# PMIC_RK809_RK3566_DDR4.net
KiCad netlist of a schematic drawn in Altium Designer
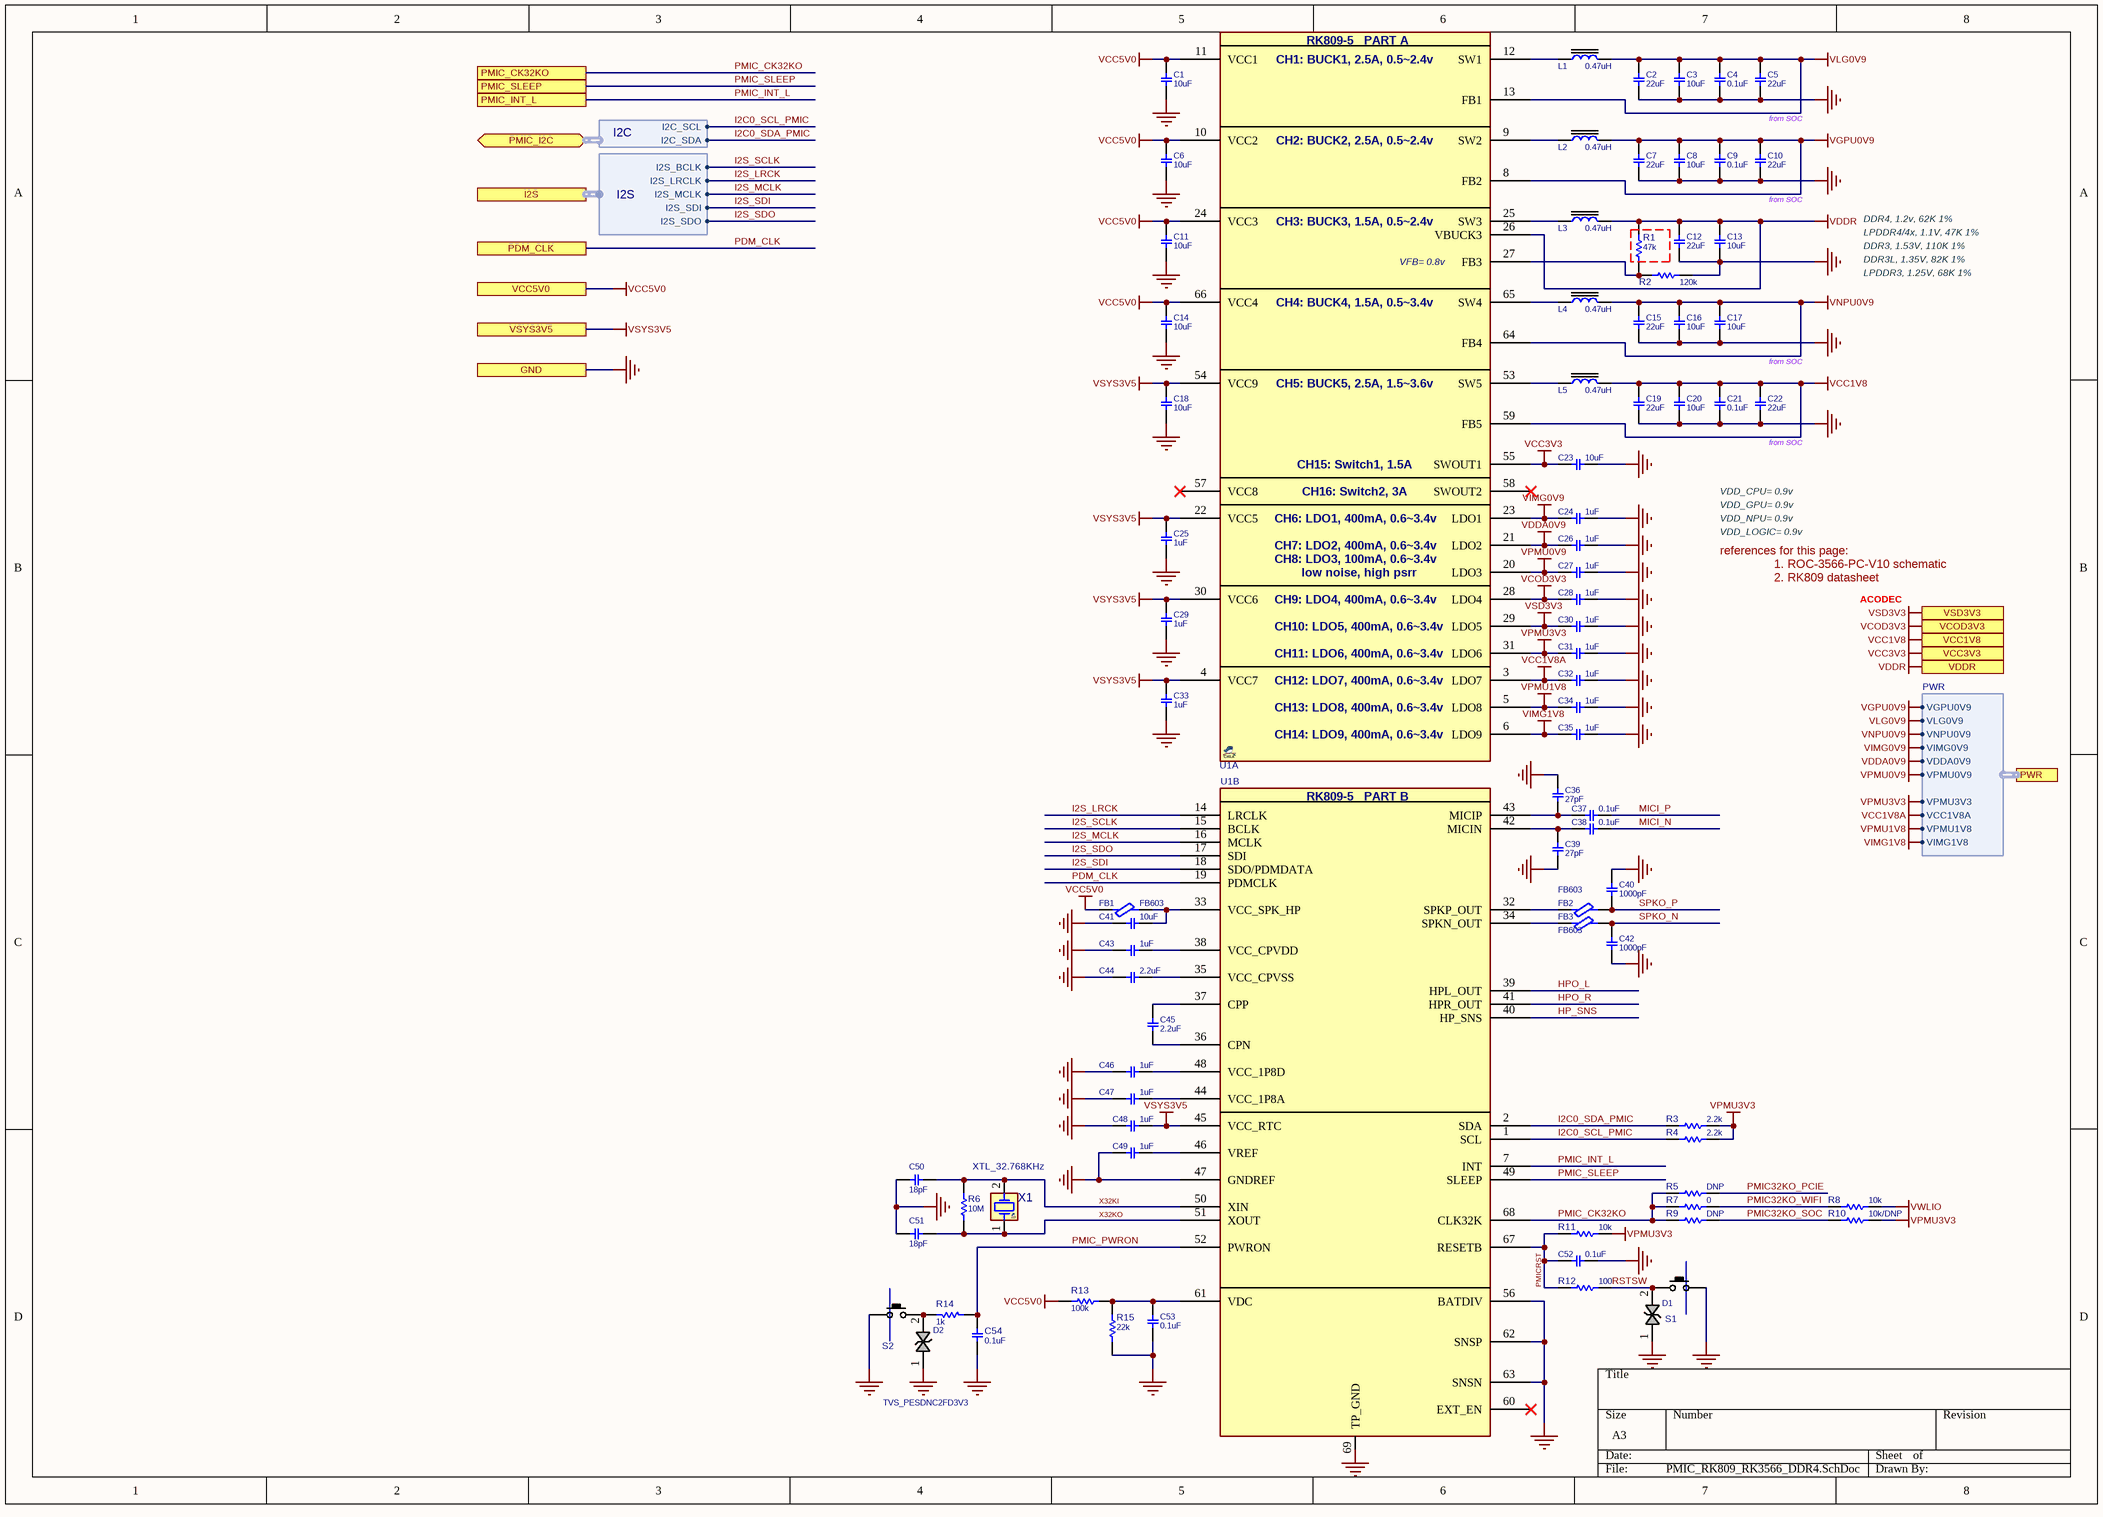
[diagram p0: PMIC_RK809_RK3566_DDR4.SchDoc]

(export (version "E")
  (design (tool "Eeschema 10.0.6"))
  (components
    (comp (ref "C1")
      (value "10uF")
      (footprint "C0402")
      (description "CAP, MLCC")
      (fields (field (name "MANF_P#") "CL05A106MP5NUNC") (field (name "MANF") "Samsung"))
      (libsource (lib "passive_smd") (part "CAP_SMD_MLCC"))
    )
    (comp (ref "C2")
      (value "22uF")
      (footprint "C0402")
      (description "CAP, MLCC")
      (fields (field (name "MANF_P#") "GRM158R61A226ME15") (field (name "MANF") "Murata"))
      (libsource (lib "passive_smd") (part "CAP_SMD_MLCC"))
    )
    (comp (ref "C3")
      (value "10uF")
      (footprint "C0402")
      (description "CAP, MLCC")
      (fields (field (name "MANF_P#") "CL05A106MP5NUNC") (field (name "MANF") "Samsung"))
      (libsource (lib "passive_smd") (part "CAP_SMD_MLCC"))
    )
    (comp (ref "C4")
      (value "0.1uF")
      (footprint "C0402")
      (description "CAP, MLCC")
      (fields (field (name "MANF_P#") "GRM155R61E104") (field (name "MANF") "Murata"))
      (libsource (lib "passive_smd") (part "CAP_SMD_MLCC"))
    )
    (comp (ref "C5")
      (value "22uF")
      (footprint "C0402")
      (description "CAP, MLCC")
      (fields (field (name "MANF_P#") "GRM158R61A226ME15") (field (name "MANF") "Murata"))
      (libsource (lib "passive_smd") (part "CAP_SMD_MLCC"))
    )
    (comp (ref "C6")
      (value "10uF")
      (footprint "C0402")
      (description "CAP, MLCC")
      (fields (field (name "MANF_P#") "CL05A106MP5NUNC") (field (name "MANF") "Samsung"))
      (libsource (lib "passive_smd") (part "CAP_SMD_MLCC"))
    )
    (comp (ref "C7")
      (value "22uF")
      (footprint "C0402")
      (description "CAP, MLCC")
      (fields (field (name "MANF_P#") "GRM158R61A226ME15") (field (name "MANF") "Murata"))
      (libsource (lib "passive_smd") (part "CAP_SMD_MLCC"))
    )
    (comp (ref "C8")
      (value "10uF")
      (footprint "C0402")
      (description "CAP, MLCC")
      (fields (field (name "MANF_P#") "CL05A106MP5NUNC") (field (name "MANF") "Samsung"))
      (libsource (lib "passive_smd") (part "CAP_SMD_MLCC"))
    )
    (comp (ref "C9")
      (value "0.1uF")
      (footprint "C0402")
      (description "CAP, MLCC")
      (fields (field (name "MANF_P#") "GRM155R61E104") (field (name "MANF") "Murata"))
      (libsource (lib "passive_smd") (part "CAP_SMD_MLCC"))
    )
    (comp (ref "C10")
      (value "22uF")
      (footprint "C0402")
      (description "CAP, MLCC")
      (fields (field (name "MANF_P#") "GRM158R61A226ME15") (field (name "MANF") "Murata"))
      (libsource (lib "passive_smd") (part "CAP_SMD_MLCC"))
    )
    (comp (ref "C11")
      (value "10uF")
      (footprint "C0402")
      (description "CAP, MLCC")
      (fields (field (name "MANF_P#") "CL05A106MP5NUNC") (field (name "MANF") "Samsung"))
      (libsource (lib "passive_smd") (part "CAP_SMD_MLCC"))
    )
    (comp (ref "C12")
      (value "22uF")
      (footprint "C0402")
      (description "CAP, MLCC")
      (fields (field (name "MANF_P#") "GRM158R61A226ME15") (field (name "MANF") "Murata"))
      (libsource (lib "passive_smd") (part "CAP_SMD_MLCC"))
    )
    (comp (ref "C13")
      (value "10uF")
      (footprint "C0402")
      (description "CAP, MLCC")
      (fields (field (name "MANF_P#") "CL05A106MP5NUNC") (field (name "MANF") "Samsung"))
      (libsource (lib "passive_smd") (part "CAP_SMD_MLCC"))
    )
    (comp (ref "C14")
      (value "10uF")
      (footprint "C0402")
      (description "CAP, MLCC")
      (fields (field (name "MANF_P#") "CL05A106MP5NUNC") (field (name "MANF") "Samsung"))
      (libsource (lib "passive_smd") (part "CAP_SMD_MLCC"))
    )
    (comp (ref "C15")
      (value "22uF")
      (footprint "C0402")
      (description "CAP, MLCC")
      (fields (field (name "MANF_P#") "GRM158R61A226ME15") (field (name "MANF") "Murata"))
      (libsource (lib "passive_smd") (part "CAP_SMD_MLCC"))
    )
    (comp (ref "C16")
      (value "10uF")
      (footprint "C0402")
      (description "CAP, MLCC")
      (fields (field (name "MANF_P#") "CL05A106MP5NUNC") (field (name "MANF") "Samsung"))
      (libsource (lib "passive_smd") (part "CAP_SMD_MLCC"))
    )
    (comp (ref "C17")
      (value "10uF")
      (footprint "C0402")
      (description "CAP, MLCC")
      (fields (field (name "MANF_P#") "CL05A106MP5NUNC") (field (name "MANF") "Samsung"))
      (libsource (lib "passive_smd") (part "CAP_SMD_MLCC"))
    )
    (comp (ref "C18")
      (value "10uF")
      (footprint "C0402")
      (description "CAP, MLCC")
      (fields (field (name "MANF_P#") "CL05A106MP5NUNC") (field (name "MANF") "Samsung"))
      (libsource (lib "passive_smd") (part "CAP_SMD_MLCC"))
    )
    (comp (ref "C19")
      (value "22uF")
      (footprint "C0402")
      (description "CAP, MLCC")
      (fields (field (name "MANF_P#") "GRM158R61A226ME15") (field (name "MANF") "Murata"))
      (libsource (lib "passive_smd") (part "CAP_SMD_MLCC"))
    )
    (comp (ref "C20")
      (value "10uF")
      (footprint "C0402")
      (description "CAP, MLCC")
      (fields (field (name "MANF_P#") "CL05A106MP5NUNC") (field (name "MANF") "Samsung"))
      (libsource (lib "passive_smd") (part "CAP_SMD_MLCC"))
    )
    (comp (ref "C21")
      (value "0.1uF")
      (footprint "C0402")
      (description "CAP, MLCC")
      (fields (field (name "MANF_P#") "GRM155R61E104") (field (name "MANF") "Murata"))
      (libsource (lib "passive_smd") (part "CAP_SMD_MLCC"))
    )
    (comp (ref "C22")
      (value "22uF")
      (footprint "C0402")
      (description "CAP, MLCC")
      (fields (field (name "MANF_P#") "GRM158R61A226ME15") (field (name "MANF") "Murata"))
      (libsource (lib "passive_smd") (part "CAP_SMD_MLCC"))
    )
    (comp (ref "C23")
      (value "10uF")
      (footprint "C0402")
      (description "CAP, MLCC")
      (fields (field (name "MANF_P#") "CL05A106MP5NUNC") (field (name "MANF") "Samsung"))
      (libsource (lib "passive_smd") (part "CAP_SMD_MLCC"))
    )
    (comp (ref "C24")
      (value "1uF")
      (footprint "C0402")
      (description "CAP, MLCC")
      (fields (field (name "MANF_P#") "CL05A105KO5NNND") (field (name "MANF") "Samsung"))
      (libsource (lib "passive_smd") (part "CAP_SMD_MLCC"))
    )
    (comp (ref "C25")
      (value "1uF")
      (footprint "C0402")
      (description "CAP, MLCC")
      (fields (field (name "MANF_P#") "CL05A105KO5NNND") (field (name "MANF") "Samsung"))
      (libsource (lib "passive_smd") (part "CAP_SMD_MLCC"))
    )
    (comp (ref "C26")
      (value "1uF")
      (footprint "C0402")
      (description "CAP, MLCC")
      (fields (field (name "MANF_P#") "CL05A105KO5NNND") (field (name "MANF") "Samsung"))
      (libsource (lib "passive_smd") (part "CAP_SMD_MLCC"))
    )
    (comp (ref "C27")
      (value "1uF")
      (footprint "C0402")
      (description "CAP, MLCC")
      (fields (field (name "MANF_P#") "CL05A105KO5NNND") (field (name "MANF") "Samsung"))
      (libsource (lib "passive_smd") (part "CAP_SMD_MLCC"))
    )
    (comp (ref "C28")
      (value "1uF")
      (footprint "C0402")
      (description "CAP, MLCC")
      (fields (field (name "MANF_P#") "CL05A105KO5NNND") (field (name "MANF") "Samsung"))
      (libsource (lib "passive_smd") (part "CAP_SMD_MLCC"))
    )
    (comp (ref "C29")
      (value "1uF")
      (footprint "C0402")
      (description "CAP, MLCC")
      (fields (field (name "MANF_P#") "CL05A105KO5NNND") (field (name "MANF") "Samsung"))
      (libsource (lib "passive_smd") (part "CAP_SMD_MLCC"))
    )
    (comp (ref "C30")
      (value "1uF")
      (footprint "C0402")
      (description "CAP, MLCC")
      (fields (field (name "MANF_P#") "CL05A105KO5NNND") (field (name "MANF") "Samsung"))
      (libsource (lib "passive_smd") (part "CAP_SMD_MLCC"))
    )
    (comp (ref "C31")
      (value "1uF")
      (footprint "C0402")
      (description "CAP, MLCC")
      (fields (field (name "MANF_P#") "CL05A105KO5NNND") (field (name "MANF") "Samsung"))
      (libsource (lib "passive_smd") (part "CAP_SMD_MLCC"))
    )
    (comp (ref "C32")
      (value "1uF")
      (footprint "C0402")
      (description "CAP, MLCC")
      (fields (field (name "MANF_P#") "CL05A105KO5NNND") (field (name "MANF") "Samsung"))
      (libsource (lib "passive_smd") (part "CAP_SMD_MLCC"))
    )
    (comp (ref "C33")
      (value "1uF")
      (footprint "C0402")
      (description "CAP, MLCC")
      (fields (field (name "MANF_P#") "CL05A105KO5NNND") (field (name "MANF") "Samsung"))
      (libsource (lib "passive_smd") (part "CAP_SMD_MLCC"))
    )
    (comp (ref "C34")
      (value "1uF")
      (footprint "C0402")
      (description "CAP, MLCC")
      (fields (field (name "MANF_P#") "CL05A105KO5NNND") (field (name "MANF") "Samsung"))
      (libsource (lib "passive_smd") (part "CAP_SMD_MLCC"))
    )
    (comp (ref "C35")
      (value "1uF")
      (footprint "C0402")
      (description "CAP, MLCC")
      (fields (field (name "MANF_P#") "CL05A105KO5NNND") (field (name "MANF") "Samsung"))
      (libsource (lib "passive_smd") (part "CAP_SMD_MLCC"))
    )
    (comp (ref "C36")
      (value "27pF")
      (footprint "C0402")
      (description "CAP, MLCC")
      (fields (field (name "MANF_P#") "CC0402JRNPO9BN270") (field (name "MANF") "Yageo"))
      (libsource (lib "passive_smd") (part "CAP_SMD_MLCC"))
    )
    (comp (ref "C37")
      (value "0.1uF")
      (footprint "C0402")
      (description "CAP, MLCC")
      (fields (field (name "MANF_P#") "GRM155R61E104") (field (name "MANF") "Murata"))
      (libsource (lib "passive_smd") (part "CAP_SMD_MLCC"))
    )
    (comp (ref "C38")
      (value "0.1uF")
      (footprint "C0402")
      (description "CAP, MLCC")
      (fields (field (name "MANF_P#") "GRM155R61E104") (field (name "MANF") "Murata"))
      (libsource (lib "passive_smd") (part "CAP_SMD_MLCC"))
    )
    (comp (ref "C39")
      (value "27pF")
      (footprint "C0402")
      (description "CAP, MLCC")
      (fields (field (name "MANF_P#") "CC0402JRNPO9BN270") (field (name "MANF") "Yageo"))
      (libsource (lib "passive_smd") (part "CAP_SMD_MLCC"))
    )
    (comp (ref "C40")
      (value "1000pF")
      (footprint "C0402")
      (description "CAP, MLCC")
      (fields (field (name "MANF_P#") "CC0402JRNPO9BN102") (field (name "MANF") "Yageo"))
      (libsource (lib "passive_smd") (part "CAP_SMD_MLCC"))
    )
    (comp (ref "C41")
      (value "10uF")
      (footprint "C0402")
      (description "CAP, MLCC")
      (fields (field (name "MANF_P#") "CL05A106MP5NUNC") (field (name "MANF") "Samsung"))
      (libsource (lib "passive_smd") (part "CAP_SMD_MLCC"))
    )
    (comp (ref "C42")
      (value "1000pF")
      (footprint "C0402")
      (description "CAP, MLCC")
      (fields (field (name "MANF_P#") "CC0402JRNPO9BN102") (field (name "MANF") "Yageo"))
      (libsource (lib "passive_smd") (part "CAP_SMD_MLCC"))
    )
    (comp (ref "C43")
      (value "1uF")
      (footprint "C0402")
      (description "CAP, MLCC")
      (fields (field (name "MANF_P#") "CL05A105KO5NNND") (field (name "MANF") "Samsung"))
      (libsource (lib "passive_smd") (part "CAP_SMD_MLCC"))
    )
    (comp (ref "C44")
      (value "2.2uF")
      (footprint "C0402")
      (description "CAP, MLCC")
      (fields (field (name "MANF_P#") "CL05A225MP5NNNC") (field (name "MANF") "Samsung"))
      (libsource (lib "passive_smd") (part "CAP_SMD_MLCC"))
    )
    (comp (ref "C45")
      (value "2.2uF")
      (footprint "C0402")
      (description "CAP, MLCC")
      (fields (field (name "MANF_P#") "CL05A225MP5NNNC") (field (name "MANF") "Samsung"))
      (libsource (lib "passive_smd") (part "CAP_SMD_MLCC"))
    )
    (comp (ref "C46")
      (value "1uF")
      (footprint "C0402")
      (description "CAP, MLCC")
      (fields (field (name "MANF_P#") "CL05A105KO5NNND") (field (name "MANF") "Samsung"))
      (libsource (lib "passive_smd") (part "CAP_SMD_MLCC"))
    )
    (comp (ref "C47")
      (value "1uF")
      (footprint "C0402")
      (description "CAP, MLCC")
      (fields (field (name "MANF_P#") "CL05A105KO5NNND") (field (name "MANF") "Samsung"))
      (libsource (lib "passive_smd") (part "CAP_SMD_MLCC"))
    )
    (comp (ref "C48")
      (value "1uF")
      (footprint "C0402")
      (description "CAP, MLCC")
      (fields (field (name "MANF_P#") "CL05A105KO5NNND") (field (name "MANF") "Samsung"))
      (libsource (lib "passive_smd") (part "CAP_SMD_MLCC"))
    )
    (comp (ref "C49")
      (value "1uF")
      (footprint "C0402")
      (description "CAP, MLCC")
      (fields (field (name "MANF_P#") "CL05A105KO5NNND") (field (name "MANF") "Samsung"))
      (libsource (lib "passive_smd") (part "CAP_SMD_MLCC"))
    )
    (comp (ref "C50")
      (value "18pF")
      (footprint "C0402")
      (description "CAP, MLCC")
      (fields (field (name "MANF_P#") "CC0402JRNPO9BN180") (field (name "MANF") "Yageo"))
      (libsource (lib "mlcc_smd_passive") (part "CAP_SMD_MLCC"))
    )
    (comp (ref "C51")
      (value "18pF")
      (footprint "C0402")
      (description "CAP, MLCC")
      (fields (field (name "MANF_P#") "CC0402JRNPO9BN180") (field (name "MANF") "Yageo"))
      (libsource (lib "mlcc_smd_passive") (part "CAP_SMD_MLCC"))
    )
    (comp (ref "C52")
      (value "0.1uF")
      (footprint "C0402")
      (description "CAP, MLCC")
      (fields (field (name "MANF_P#") "GRM155R61E104") (field (name "MANF") "Murata"))
      (libsource (lib "passive_smd") (part "CAP_SMD_MLCC"))
    )
    (comp (ref "C53")
      (value "0.1uF")
      (footprint "C0402")
      (description "CAP, MLCC")
      (fields (field (name "MANF_P#") "GRM155R61E104") (field (name "MANF") "Murata"))
      (libsource (lib "passive_smd") (part "CAP_SMD_MLCC"))
    )
    (comp (ref "C54")
      (value "0.1uF")
      (footprint "C0402")
      (description "CAP, MLCC")
      (fields (field (name "MANF_P#") "GRM155R71H104KE14D") (field (name "MANF") "Murata"))
      (libsource (lib "mlcc_smd_passive") (part "CAP_SMD_MLCC_100n50TDK"))
    )
    (comp (ref "D1")
      (value "TVS_PESDNC2FD3V3")
      (footprint "ESD0402")
      (description "TVS, ESD PROTECT, Bidirectional")
      (fields (field (name "MANF_P#") "PESDNC2FD3V3BS"))
      (libsource (lib "protect_tvs_esd_fuse") (part "TVS_PESDNC2FD3V3"))
    )
    (comp (ref "D2")
      (value "TVS_PESDNC2FD3V3")
      (footprint "ESD0402")
      (description "TVS, ESD PROTECT, Bidirectional")
      (fields (field (name "MANF_P#") "PESDNC2FD3V3BS"))
      (libsource (lib "protect_tvs_esd_fuse") (part "TVS_PESDNC2FD3V3"))
    )
    (comp (ref "FB1")
      (value "FB603")
      (footprint "L0603")
      (description "FERRITE_Bead, 0603, 1.3A, 150mOhm, 600@100MHz")
      (fields (field (name "MANF_P#") "ACMS160808A1213A"))
      (libsource (lib "emi_filter") (part "FBEAD_SMD_BLM18KG601"))
    )
    (comp (ref "FB2")
      (value "FB603")
      (footprint "L0603")
      (description "FERRITE_Bead, 0603, 1.3A, 150mOhm, 600@100MHz")
      (fields (field (name "MANF_P#") "CBM160808U181T"))
      (libsource (lib "emi_filter") (part "FBEAD_SMD_BLM18KG601"))
    )
    (comp (ref "FB3")
      (value "FB603")
      (footprint "L0603")
      (description "FERRITE_Bead, 0603, 1.3A, 150mOhm, 600@100MHz")
      (fields (field (name "MANF_P#") "CBM160808U181T"))
      (libsource (lib "emi_filter") (part "FBEAD_SMD_BLM18KG601"))
    )
    (comp (ref "L1")
      (value "0.47uH")
      (footprint "L0806")
      (description "INDUCTOR")
      (fields (field (name "MANF_P#") "DFE201610E-R47M") (field (name "MANF") "Murata"))
      (libsource (lib "inductor_power") (part "IND_SMD_2.2uH_2.6A"))
    )
    (comp (ref "L2")
      (value "0.47uH")
      (footprint "L0806")
      (description "INDUCTOR")
      (fields (field (name "MANF_P#") "DFE201610E-R47M") (field (name "MANF") "Murata"))
      (libsource (lib "inductor_power") (part "IND_SMD_2.2uH_2.6A"))
    )
    (comp (ref "L3")
      (value "0.47uH")
      (footprint "L0806")
      (description "INDUCTOR")
      (fields (field (name "MANF_P#") "DFE201610E-R47M") (field (name "MANF") "Murata"))
      (libsource (lib "inductor_power") (part "IND_SMD_2.2uH_2.6A"))
    )
    (comp (ref "L4")
      (value "0.47uH")
      (footprint "L0806")
      (description "INDUCTOR")
      (fields (field (name "MANF_P#") "DFE201610E-R47M") (field (name "MANF") "Murata"))
      (libsource (lib "inductor_power") (part "IND_SMD_2.2uH_2.6A"))
    )
    (comp (ref "L5")
      (value "0.47uH")
      (footprint "L0806")
      (description "INDUCTOR")
      (fields (field (name "MANF_P#") "DFE201610E-R47M") (field (name "MANF") "Murata"))
      (libsource (lib "inductor_power") (part "IND_SMD_2.2uH_2.6A"))
    )
    (comp (ref "R1")
      (value "47k")
      (footprint "R0402")
      (description "RESISTOR, SMD")
      (libsource (lib "passive_res_smd") (part "RES_SMD"))
    )
    (comp (ref "R2")
      (value "120k")
      (footprint "R0402")
      (description "RESISTOR, SMD")
      (libsource (lib "passive_res_smd") (part "RES_SMD"))
    )
    (comp (ref "R3")
      (value "2.2k")
      (footprint "R0402")
      (description "RESISTOR, SMD")
      (libsource (lib "passive_res_smd") (part "RES_SMD"))
    )
    (comp (ref "R4")
      (value "2.2k")
      (footprint "R0402")
      (description "RESISTOR, SMD")
      (libsource (lib "passive_res_smd") (part "RES_SMD"))
    )
    (comp (ref "R5")
      (value "DNP")
      (footprint "R0402")
      (description "RESISTOR, SMD")
      (libsource (lib "passive_res_smd") (part "RES_SMD"))
    )
    (comp (ref "R6")
      (value "10M")
      (footprint "R0402")
      (description "RESISTOR, SMD")
      (libsource (lib "passive_res_smd") (part "RES_SMD"))
    )
    (comp (ref "R7")
      (value "0")
      (footprint "R0402")
      (description "RESISTOR, SMD")
      (libsource (lib "passive_res_smd") (part "RES_SMD"))
    )
    (comp (ref "R8")
      (value "10k")
      (footprint "R0402")
      (description "RESISTOR, SMD")
      (libsource (lib "passive_res_smd") (part "RES_SMD"))
    )
    (comp (ref "R9")
      (value "DNP")
      (footprint "R0402")
      (description "RESISTOR, SMD")
      (libsource (lib "passive_res_smd") (part "RES_SMD"))
    )
    (comp (ref "R10")
      (value "10k/DNP")
      (footprint "R0402")
      (description "RESISTOR, SMD")
      (libsource (lib "passive_res_smd") (part "RES_SMD"))
    )
    (comp (ref "R11")
      (value "10k")
      (footprint "R0402")
      (description "RESISTOR, SMD")
      (libsource (lib "passive_res_smd") (part "RES_SMD"))
    )
    (comp (ref "R12")
      (value "100")
      (footprint "R0402")
      (description "RESISTOR, SMD")
      (libsource (lib "passive_res_smd") (part "RES_SMD"))
    )
    (comp (ref "R13")
      (value "100k")
      (footprint "R0402")
      (description "RESISTOR, SMD")
      (libsource (lib "passive_res_smd") (part "RES_SMD"))
    )
    (comp (ref "R14")
      (value "1k")
      (footprint "R0402")
      (description "RESISTOR, SMD")
      (libsource (lib "passive_res_smd") (part "RES_SMD"))
    )
    (comp (ref "R15")
      (value "22k")
      (footprint "R0402")
      (description "RESISTOR, SMD")
      (libsource (lib "passive_res_smd") (part "RES_SMD"))
    )
    (comp (ref "S1")
      (value "PUSHBUTTON")
      (footprint "SWPBS_SPST_3X2X1")
      (description "SWITCH, PUSH BUTTON, TACTILE, SMD, SPST, 3X2.5X1.2mm")
      (fields (field (name "MANF") "OMRON") (field (name "MANF_P#") "B3U-1000P"))
      (libsource (lib "") (part "SWPBS_SPST_3X2_B3U-1000P_1"))
    )
    (comp (ref "S2")
      (value "PUSHBUTTON")
      (footprint "SWPBS_SPST_3X2X1")
      (description "SWITCH, PUSH BUTTON, TACTILE, SMD, SPST, 3X2.5X1.2mm")
      (fields (field (name "MANF") "OMRON") (field (name "MANF_P#") "B3U-1000P"))
      (libsource (lib "switch_tact_PUSHB") (part "SWPBS_SPST_3X2_B3U-1000P"))
    )
    (comp (ref "U1")
      (value "RK809-5")
      (footprint "QFN35_68T")
      (description "IC, Regulator PMIC, for RK3566")
      (fields (field (name "MANF") "Rockchip"))
      (libsource (lib "pwr_reg_pmic") (part "RK809-5_QFN68"))
    )
    (comp (ref "X1")
      (value "XTL_32.768KHz")
      (footprint "XTL_2_1610")
      (description "Crystal, 32.768KHz, 9pF, 20PPM")
      (fields (field (name "MANF") "ABRACON") (field (name "MANF_P#") "ABS05-32.768KHZ-9-T"))
      (libsource (lib "crystal") (part "XTL_2_32.768_1610A"))
    )
  )
  (nets
    (net (code "4") (name "/HPO_L") (class "Default")
      (node (ref "U1") (pin "39") (pinfunction "HPL_OUT_39") (pintype "passive"))
    )
    (net (code "5") (name "/HPO_R") (class "Default")
      (node (ref "U1") (pin "41") (pinfunction "HPR_OUT_41") (pintype "passive"))
    )
    (net (code "6") (name "/HP_SNS") (class "Default")
      (node (ref "U1") (pin "40") (pinfunction "HP_SNS_40") (pintype "passive"))
    )
    (net (code "7") (name "/I2C0_SCL_PMIC") (class "Default")
      (node (ref "R4") (pin "2") (pinfunction "2_2") (pintype "passive"))
      (node (ref "U1") (pin "1") (pinfunction "SCL_1") (pintype "passive"))
    )
    (net (code "8") (name "/I2C0_SDA_PMIC") (class "Default")
      (node (ref "R3") (pin "2") (pinfunction "2_2") (pintype "passive"))
      (node (ref "U1") (pin "2") (pinfunction "SDA_2") (pintype "passive"))
    )
    (net (code "9") (name "/I2S_LRCK") (class "Default")
      (node (ref "U1") (pin "14") (pinfunction "LRCLK_14") (pintype "passive"))
    )
    (net (code "10") (name "/I2S_MCLK") (class "Default")
      (node (ref "U1") (pin "16") (pinfunction "MCLK_16") (pintype "passive"))
    )
    (net (code "11") (name "/I2S_SCLK") (class "Default")
      (node (ref "U1") (pin "15") (pinfunction "BCLK_15") (pintype "passive"))
    )
    (net (code "12") (name "/I2S_SDI") (class "Default")
      (node (ref "U1") (pin "18") (pinfunction "SDO/PDMDATA_18") (pintype "passive"))
    )
    (net (code "13") (name "/I2S_SDO") (class "Default")
      (node (ref "U1") (pin "17") (pinfunction "SDI_17") (pintype "passive"))
    )
    (net (code "14") (name "/MICI_N") (class "Default")
      (node (ref "C38") (pin "1") (pinfunction "1_1") (pintype "passive"))
    )
    (net (code "15") (name "/MICI_P") (class "Default")
      (node (ref "C37") (pin "1") (pinfunction "1_1") (pintype "passive"))
    )
    (net (code "16") (name "/PDM_CLK") (class "Default")
      (node (ref "U1") (pin "19") (pinfunction "PDMCLK_19") (pintype "passive"))
    )
    (net (code "17") (name "/PMIC32KO_PCIE") (class "Default")
      (node (ref "R5") (pin "1") (pinfunction "1_1") (pintype "passive"))
    )
    (net (code "18") (name "/PMIC32KO_SOC") (class "Default")
      (node (ref "R10") (pin "2") (pinfunction "2_2") (pintype "passive"))
      (node (ref "R9") (pin "1") (pinfunction "1_1") (pintype "passive"))
    )
    (net (code "19") (name "/PMIC32KO_WIFI") (class "Default")
      (node (ref "R7") (pin "1") (pinfunction "1_1") (pintype "passive"))
      (node (ref "R8") (pin "2") (pinfunction "2_2") (pintype "passive"))
    )
    (net (code "20") (name "/PMICRST") (class "Default")
      (node (ref "C52") (pin "1") (pinfunction "1_1") (pintype "passive"))
      (node (ref "R11") (pin "1") (pinfunction "1_1") (pintype "passive"))
      (node (ref "R12") (pin "1") (pinfunction "1_1") (pintype "passive"))
      (node (ref "U1") (pin "67") (pinfunction "RESETB_67") (pintype "passive"))
    )
    (net (code "21") (name "/PMIC_CK32KO") (class "Default")
      (node (ref "R5") (pin "2") (pinfunction "2_2") (pintype "passive"))
      (node (ref "R7") (pin "2") (pinfunction "2_2") (pintype "passive"))
      (node (ref "R9") (pin "2") (pinfunction "2_2") (pintype "passive"))
      (node (ref "U1") (pin "68") (pinfunction "CLK32K_68") (pintype "passive"))
    )
    (net (code "22") (name "/PMIC_INT_L") (class "Default")
      (node (ref "U1") (pin "7") (pinfunction "INT_7") (pintype "passive"))
    )
    (net (code "23") (name "/PMIC_PWRON") (class "Default")
      (node (ref "C54") (pin "1") (pinfunction "1_1") (pintype "passive"))
      (node (ref "R14") (pin "2") (pinfunction "2_2") (pintype "passive"))
      (node (ref "U1") (pin "52") (pinfunction "PWRON_52") (pintype "passive"))
    )
    (net (code "24") (name "/PMIC_SLEEP") (class "Default")
      (node (ref "U1") (pin "49") (pinfunction "SLEEP_49") (pintype "passive"))
    )
    (net (code "25") (name "/RSTSW") (class "Default")
      (node (ref "D1") (pin "2") (pinfunction "2_2") (pintype "passive"))
      (node (ref "R12") (pin "2") (pinfunction "2_2") (pintype "passive"))
      (node (ref "S1") (pin "1") (pinfunction "P1_1") (pintype "passive"))
    )
    (net (code "26") (name "/SPKO_N") (class "Default")
      (node (ref "C42") (pin "1") (pinfunction "1_1") (pintype "passive"))
      (node (ref "FB3") (pin "2") (pinfunction "2_2") (pintype "passive"))
    )
    (net (code "27") (name "/SPKO_P") (class "Default")
      (node (ref "C40") (pin "2") (pinfunction "2_2") (pintype "passive"))
      (node (ref "FB2") (pin "2") (pinfunction "2_2") (pintype "passive"))
    )
    (net (code "28") (name "/X32KI") (class "Default")
      (node (ref "C50") (pin "1") (pinfunction "1_1") (pintype "passive"))
      (node (ref "R6") (pin "2") (pinfunction "2_2") (pintype "passive"))
      (node (ref "U1") (pin "50") (pinfunction "XIN_50") (pintype "passive"))
      (node (ref "X1") (pin "2") (pinfunction "OSC2_2") (pintype "passive"))
    )
    (net (code "29") (name "/X32KO") (class "Default")
      (node (ref "C51") (pin "1") (pinfunction "1_1") (pintype "passive"))
      (node (ref "R6") (pin "1") (pinfunction "1_1") (pintype "passive"))
      (node (ref "U1") (pin "51") (pinfunction "XOUT_51") (pintype "passive"))
      (node (ref "X1") (pin "1") (pinfunction "OSC1_1") (pintype "passive"))
    )
    (net (code "33") (name "GND") (class "Default")
      (node (ref "C1") (pin "1") (pinfunction "1_1") (pintype "passive"))
      (node (ref "C10") (pin "1") (pinfunction "1_1") (pintype "passive"))
      (node (ref "C11") (pin "1") (pinfunction "1_1") (pintype "passive"))
      (node (ref "C12") (pin "1") (pinfunction "1_1") (pintype "passive"))
      (node (ref "C13") (pin "1") (pinfunction "1_1") (pintype "passive"))
      (node (ref "C14") (pin "1") (pinfunction "1_1") (pintype "passive"))
      (node (ref "C15") (pin "1") (pinfunction "1_1") (pintype "passive"))
      (node (ref "C16") (pin "1") (pinfunction "1_1") (pintype "passive"))
      (node (ref "C17") (pin "1") (pinfunction "1_1") (pintype "passive"))
      (node (ref "C18") (pin "1") (pinfunction "1_1") (pintype "passive"))
      (node (ref "C19") (pin "1") (pinfunction "1_1") (pintype "passive"))
      (node (ref "C2") (pin "1") (pinfunction "1_1") (pintype "passive"))
      (node (ref "C20") (pin "1") (pinfunction "1_1") (pintype "passive"))
      (node (ref "C21") (pin "1") (pinfunction "1_1") (pintype "passive"))
      (node (ref "C22") (pin "1") (pinfunction "1_1") (pintype "passive"))
      (node (ref "C23") (pin "1") (pinfunction "1_1") (pintype "passive"))
      (node (ref "C24") (pin "1") (pinfunction "1_1") (pintype "passive"))
      (node (ref "C25") (pin "1") (pinfunction "1_1") (pintype "passive"))
      (node (ref "C26") (pin "1") (pinfunction "1_1") (pintype "passive"))
      (node (ref "C27") (pin "1") (pinfunction "1_1") (pintype "passive"))
      (node (ref "C28") (pin "1") (pinfunction "1_1") (pintype "passive"))
      (node (ref "C29") (pin "1") (pinfunction "1_1") (pintype "passive"))
      (node (ref "C3") (pin "1") (pinfunction "1_1") (pintype "passive"))
      (node (ref "C30") (pin "1") (pinfunction "1_1") (pintype "passive"))
      (node (ref "C31") (pin "1") (pinfunction "1_1") (pintype "passive"))
      (node (ref "C32") (pin "1") (pinfunction "1_1") (pintype "passive"))
      (node (ref "C33") (pin "1") (pinfunction "1_1") (pintype "passive"))
      (node (ref "C34") (pin "1") (pinfunction "1_1") (pintype "passive"))
      (node (ref "C35") (pin "1") (pinfunction "1_1") (pintype "passive"))
      (node (ref "C36") (pin "1") (pinfunction "1_1") (pintype "passive"))
      (node (ref "C39") (pin "2") (pinfunction "2_2") (pintype "passive"))
      (node (ref "C4") (pin "1") (pinfunction "1_1") (pintype "passive"))
      (node (ref "C40") (pin "1") (pinfunction "1_1") (pintype "passive"))
      (node (ref "C41") (pin "1") (pinfunction "1_1") (pintype "passive"))
      (node (ref "C42") (pin "2") (pinfunction "2_2") (pintype "passive"))
      (node (ref "C43") (pin "2") (pinfunction "2_2") (pintype "passive"))
      (node (ref "C44") (pin "2") (pinfunction "2_2") (pintype "passive"))
      (node (ref "C46") (pin "2") (pinfunction "2_2") (pintype "passive"))
      (node (ref "C47") (pin "2") (pinfunction "2_2") (pintype "passive"))
      (node (ref "C48") (pin "2") (pinfunction "2_2") (pintype "passive"))
      (node (ref "C49") (pin "2") (pinfunction "2_2") (pintype "passive"))
      (node (ref "C5") (pin "1") (pinfunction "1_1") (pintype "passive"))
      (node (ref "C50") (pin "2") (pinfunction "2_2") (pintype "passive"))
      (node (ref "C51") (pin "2") (pinfunction "2_2") (pintype "passive"))
      (node (ref "C52") (pin "2") (pinfunction "2_2") (pintype "passive"))
      (node (ref "C53") (pin "1") (pinfunction "1_1") (pintype "passive"))
      (node (ref "C54") (pin "2") (pinfunction "2_2") (pintype "passive"))
      (node (ref "C6") (pin "1") (pinfunction "1_1") (pintype "passive"))
      (node (ref "C7") (pin "1") (pinfunction "1_1") (pintype "passive"))
      (node (ref "C8") (pin "1") (pinfunction "1_1") (pintype "passive"))
      (node (ref "C9") (pin "1") (pinfunction "1_1") (pintype "passive"))
      (node (ref "D1") (pin "1") (pinfunction "1_1") (pintype "passive"))
      (node (ref "D2") (pin "1") (pinfunction "1_1") (pintype "passive"))
      (node (ref "R15") (pin "2") (pinfunction "2_2") (pintype "passive"))
      (node (ref "R2") (pin "1") (pinfunction "1_1") (pintype "passive"))
      (node (ref "S1") (pin "2") (pinfunction "P3_2") (pintype "passive"))
      (node (ref "S2") (pin "2") (pinfunction "P3_2") (pintype "passive"))
      (node (ref "U1") (pin "47") (pinfunction "GNDREF_47") (pintype "passive"))
      (node (ref "U1") (pin "56") (pinfunction "BATDIV_56") (pintype "passive"))
      (node (ref "U1") (pin "62") (pinfunction "SNSP_62") (pintype "passive"))
      (node (ref "U1") (pin "63") (pinfunction "SNSN_63") (pintype "passive"))
      (node (ref "U1") (pin "69") (pinfunction "TP_GND_69") (pintype "passive"))
    )
    (net (code "34") (name "Net-(S2-P1)") (class "Default")
      (node (ref "D2") (pin "2") (pinfunction "2_2") (pintype "passive"))
      (node (ref "R14") (pin "1") (pinfunction "1_1") (pintype "passive"))
      (node (ref "S2") (pin "1") (pinfunction "P1_1") (pintype "passive"))
    )
    (net (code "35") (name "Net-(U1A-FB3)") (class "Default")
      (node (ref "R1") (pin "1") (pinfunction "1_1") (pintype "passive"))
      (node (ref "R2") (pin "2") (pinfunction "2_2") (pintype "passive"))
      (node (ref "U1") (pin "27") (pinfunction "FB3_27") (pintype "passive"))
    )
    (net (code "36") (name "Net-(U1A-SW1)") (class "Default")
      (node (ref "L1") (pin "1") (pinfunction "1_1") (pintype "passive"))
      (node (ref "U1") (pin "12") (pinfunction "SW1_12") (pintype "passive"))
    )
    (net (code "37") (name "Net-(U1A-SW2)") (class "Default")
      (node (ref "L2") (pin "1") (pinfunction "1_1") (pintype "passive"))
      (node (ref "U1") (pin "9") (pinfunction "SW2_9") (pintype "passive"))
    )
    (net (code "38") (name "Net-(U1A-SW3)") (class "Default")
      (node (ref "L3") (pin "1") (pinfunction "1_1") (pintype "passive"))
      (node (ref "U1") (pin "25") (pinfunction "SW3_25") (pintype "passive"))
    )
    (net (code "39") (name "Net-(U1A-SW4)") (class "Default")
      (node (ref "L4") (pin "1") (pinfunction "1_1") (pintype "passive"))
      (node (ref "U1") (pin "65") (pinfunction "SW4_65") (pintype "passive"))
    )
    (net (code "40") (name "Net-(U1A-SW5)") (class "Default")
      (node (ref "L5") (pin "1") (pinfunction "1_1") (pintype "passive"))
      (node (ref "U1") (pin "53") (pinfunction "SW5_53") (pintype "passive"))
    )
    (net (code "41") (name "Net-(U1B-CPN)") (class "Default")
      (node (ref "C45") (pin "1") (pinfunction "1_1") (pintype "passive"))
      (node (ref "U1") (pin "36") (pinfunction "CPN_36") (pintype "passive"))
    )
    (net (code "42") (name "Net-(U1B-CPP)") (class "Default")
      (node (ref "C45") (pin "2") (pinfunction "2_2") (pintype "passive"))
      (node (ref "U1") (pin "37") (pinfunction "CPP_37") (pintype "passive"))
    )
    (net (code "43") (name "Net-(U1B-MICIN)") (class "Default")
      (node (ref "C38") (pin "2") (pinfunction "2_2") (pintype "passive"))
      (node (ref "C39") (pin "1") (pinfunction "1_1") (pintype "passive"))
      (node (ref "U1") (pin "42") (pinfunction "MICIN_42") (pintype "passive"))
    )
    (net (code "44") (name "Net-(U1B-MICIP)") (class "Default")
      (node (ref "C36") (pin "2") (pinfunction "2_2") (pintype "passive"))
      (node (ref "C37") (pin "2") (pinfunction "2_2") (pintype "passive"))
      (node (ref "U1") (pin "43") (pinfunction "MICIP_43") (pintype "passive"))
    )
    (net (code "45") (name "Net-(U1B-SPKN_OUT)") (class "Default")
      (node (ref "FB3") (pin "1") (pinfunction "1_1") (pintype "passive"))
      (node (ref "U1") (pin "34") (pinfunction "SPKN_OUT_34") (pintype "passive"))
    )
    (net (code "46") (name "Net-(U1B-SPKP_OUT)") (class "Default")
      (node (ref "FB2") (pin "1") (pinfunction "1_1") (pintype "passive"))
      (node (ref "U1") (pin "32") (pinfunction "SPKP_OUT_32") (pintype "passive"))
    )
    (net (code "47") (name "Net-(U1B-VCC_1P8A)") (class "Default")
      (node (ref "C47") (pin "1") (pinfunction "1_1") (pintype "passive"))
      (node (ref "U1") (pin "44") (pinfunction "VCC_1P8A_44") (pintype "passive"))
    )
    (net (code "48") (name "Net-(U1B-VCC_1P8D)") (class "Default")
      (node (ref "C46") (pin "1") (pinfunction "1_1") (pintype "passive"))
      (node (ref "U1") (pin "48") (pinfunction "VCC_1P8D_48") (pintype "passive"))
    )
    (net (code "49") (name "Net-(U1B-VCC_CPVDD)") (class "Default")
      (node (ref "C43") (pin "1") (pinfunction "1_1") (pintype "passive"))
      (node (ref "U1") (pin "38") (pinfunction "VCC_CPVDD_38") (pintype "passive"))
    )
    (net (code "50") (name "Net-(U1B-VCC_CPVSS)") (class "Default")
      (node (ref "C44") (pin "1") (pinfunction "1_1") (pintype "passive"))
      (node (ref "U1") (pin "35") (pinfunction "VCC_CPVSS_35") (pintype "passive"))
    )
    (net (code "51") (name "Net-(U1B-VCC_SPK_HP)") (class "Default")
      (node (ref "C41") (pin "2") (pinfunction "2_2") (pintype "passive"))
      (node (ref "FB1") (pin "2") (pinfunction "2_2") (pintype "passive"))
      (node (ref "U1") (pin "33") (pinfunction "VCC_SPK_HP_33") (pintype "passive"))
    )
    (net (code "52") (name "Net-(U1B-VDC)") (class "Default")
      (node (ref "C53") (pin "2") (pinfunction "2_2") (pintype "passive"))
      (node (ref "R13") (pin "1") (pinfunction "1_1") (pintype "passive"))
      (node (ref "R15") (pin "1") (pinfunction "1_1") (pintype "passive"))
      (node (ref "U1") (pin "61") (pinfunction "VDC_61") (pintype "passive"))
    )
    (net (code "53") (name "Net-(U1B-VREF)") (class "Default")
      (node (ref "C49") (pin "1") (pinfunction "1_1") (pintype "passive"))
      (node (ref "U1") (pin "46") (pinfunction "VREF_46") (pintype "passive"))
    )
    (net (code "54") (name "VCC1V8") (class "Default")
      (node (ref "C19") (pin "2") (pinfunction "2_2") (pintype "passive"))
      (node (ref "C20") (pin "2") (pinfunction "2_2") (pintype "passive"))
      (node (ref "C21") (pin "2") (pinfunction "2_2") (pintype "passive"))
      (node (ref "C22") (pin "2") (pinfunction "2_2") (pintype "passive"))
      (node (ref "L5") (pin "2") (pinfunction "2_2") (pintype "passive"))
      (node (ref "U1") (pin "59") (pinfunction "FB5_59") (pintype "passive"))
    )
    (net (code "55") (name "VCC1V8A") (class "Default")
      (node (ref "C32") (pin "2") (pinfunction "2_2") (pintype "passive"))
      (node (ref "U1") (pin "3") (pinfunction "LDO7_3") (pintype "passive"))
    )
    (net (code "56") (name "VCC3V3") (class "Default")
      (node (ref "C23") (pin "2") (pinfunction "2_2") (pintype "passive"))
      (node (ref "U1") (pin "55") (pinfunction "SWOUT1_55") (pintype "passive"))
    )
    (net (code "57") (name "VCC5V0") (class "Default")
      (node (ref "C1") (pin "2") (pinfunction "2_2") (pintype "passive"))
      (node (ref "C11") (pin "2") (pinfunction "2_2") (pintype "passive"))
      (node (ref "C14") (pin "2") (pinfunction "2_2") (pintype "passive"))
      (node (ref "C6") (pin "2") (pinfunction "2_2") (pintype "passive"))
      (node (ref "FB1") (pin "1") (pinfunction "1_1") (pintype "passive"))
      (node (ref "R13") (pin "2") (pinfunction "2_2") (pintype "passive"))
      (node (ref "U1") (pin "10") (pinfunction "VCC2_10") (pintype "passive"))
      (node (ref "U1") (pin "11") (pinfunction "VCC1_11") (pintype "passive"))
      (node (ref "U1") (pin "24") (pinfunction "VCC3_24") (pintype "passive"))
      (node (ref "U1") (pin "66") (pinfunction "VCC4_66") (pintype "passive"))
    )
    (net (code "58") (name "VCOD3V3") (class "Default")
      (node (ref "C28") (pin "2") (pinfunction "2_2") (pintype "passive"))
      (node (ref "U1") (pin "28") (pinfunction "LDO4_28") (pintype "passive"))
    )
    (net (code "59") (name "VDDA0V9") (class "Default")
      (node (ref "C26") (pin "2") (pinfunction "2_2") (pintype "passive"))
      (node (ref "U1") (pin "21") (pinfunction "LDO2_21") (pintype "passive"))
    )
    (net (code "60") (name "VDDR") (class "Default")
      (node (ref "C12") (pin "2") (pinfunction "2_2") (pintype "passive"))
      (node (ref "C13") (pin "2") (pinfunction "2_2") (pintype "passive"))
      (node (ref "L3") (pin "2") (pinfunction "2_2") (pintype "passive"))
      (node (ref "R1") (pin "2") (pinfunction "2_2") (pintype "passive"))
      (node (ref "U1") (pin "26") (pinfunction "VBUCK3_26") (pintype "passive"))
    )
    (net (code "61") (name "VGPU0V9") (class "Default")
      (node (ref "C10") (pin "2") (pinfunction "2_2") (pintype "passive"))
      (node (ref "C7") (pin "2") (pinfunction "2_2") (pintype "passive"))
      (node (ref "C8") (pin "2") (pinfunction "2_2") (pintype "passive"))
      (node (ref "C9") (pin "2") (pinfunction "2_2") (pintype "passive"))
      (node (ref "L2") (pin "2") (pinfunction "2_2") (pintype "passive"))
      (node (ref "U1") (pin "8") (pinfunction "FB2_8") (pintype "passive"))
    )
    (net (code "62") (name "VIMG0V9") (class "Default")
      (node (ref "C24") (pin "2") (pinfunction "2_2") (pintype "passive"))
      (node (ref "U1") (pin "23") (pinfunction "LDO1_23") (pintype "passive"))
    )
    (net (code "63") (name "VIMG1V8") (class "Default")
      (node (ref "C35") (pin "2") (pinfunction "2_2") (pintype "passive"))
      (node (ref "U1") (pin "6") (pinfunction "LDO9_6") (pintype "passive"))
    )
    (net (code "64") (name "VLG0V9") (class "Default")
      (node (ref "C2") (pin "2") (pinfunction "2_2") (pintype "passive"))
      (node (ref "C3") (pin "2") (pinfunction "2_2") (pintype "passive"))
      (node (ref "C4") (pin "2") (pinfunction "2_2") (pintype "passive"))
      (node (ref "C5") (pin "2") (pinfunction "2_2") (pintype "passive"))
      (node (ref "L1") (pin "2") (pinfunction "2_2") (pintype "passive"))
      (node (ref "U1") (pin "13") (pinfunction "FB1_13") (pintype "passive"))
    )
    (net (code "65") (name "VNPU0V9") (class "Default")
      (node (ref "C15") (pin "2") (pinfunction "2_2") (pintype "passive"))
      (node (ref "C16") (pin "2") (pinfunction "2_2") (pintype "passive"))
      (node (ref "C17") (pin "2") (pinfunction "2_2") (pintype "passive"))
      (node (ref "L4") (pin "2") (pinfunction "2_2") (pintype "passive"))
      (node (ref "U1") (pin "64") (pinfunction "FB4_64") (pintype "passive"))
    )
    (net (code "66") (name "VPMU0V9") (class "Default")
      (node (ref "C27") (pin "2") (pinfunction "2_2") (pintype "passive"))
      (node (ref "U1") (pin "20") (pinfunction "LDO3_20") (pintype "passive"))
    )
    (net (code "67") (name "VPMU1V8") (class "Default")
      (node (ref "C34") (pin "2") (pinfunction "2_2") (pintype "passive"))
      (node (ref "U1") (pin "5") (pinfunction "LDO8_5") (pintype "passive"))
    )
    (net (code "68") (name "VPMU3V3") (class "Default")
      (node (ref "C31") (pin "2") (pinfunction "2_2") (pintype "passive"))
      (node (ref "R10") (pin "1") (pinfunction "1_1") (pintype "passive"))
      (node (ref "R11") (pin "2") (pinfunction "2_2") (pintype "passive"))
      (node (ref "R3") (pin "1") (pinfunction "1_1") (pintype "passive"))
      (node (ref "R4") (pin "1") (pinfunction "1_1") (pintype "passive"))
      (node (ref "U1") (pin "31") (pinfunction "LDO6_31") (pintype "passive"))
    )
    (net (code "69") (name "VSD3V3") (class "Default")
      (node (ref "C30") (pin "2") (pinfunction "2_2") (pintype "passive"))
      (node (ref "U1") (pin "29") (pinfunction "LDO5_29") (pintype "passive"))
    )
    (net (code "70") (name "VSYS3V5") (class "Default")
      (node (ref "C18") (pin "2") (pinfunction "2_2") (pintype "passive"))
      (node (ref "C25") (pin "2") (pinfunction "2_2") (pintype "passive"))
      (node (ref "C29") (pin "2") (pinfunction "2_2") (pintype "passive"))
      (node (ref "C33") (pin "2") (pinfunction "2_2") (pintype "passive"))
      (node (ref "C48") (pin "1") (pinfunction "1_1") (pintype "passive"))
      (node (ref "U1") (pin "22") (pinfunction "VCC5_22") (pintype "passive"))
      (node (ref "U1") (pin "30") (pinfunction "VCC6_30") (pintype "passive"))
      (node (ref "U1") (pin "4") (pinfunction "VCC7_4") (pintype "passive"))
      (node (ref "U1") (pin "45") (pinfunction "VCC_RTC_45") (pintype "passive"))
      (node (ref "U1") (pin "54") (pinfunction "VCC9_54") (pintype "passive"))
    )
    (net (code "71") (name "VWLIO") (class "Default")
      (node (ref "R8") (pin "1") (pinfunction "1_1") (pintype "passive"))
    )
    (net (code "72") (name "unconnected-(U1A-SWOUT2-Pad58)") (class "Default")
      (node (ref "U1") (pin "58") (pinfunction "SWOUT2_58") (pintype "passive+no_connect"))
    )
    (net (code "73") (name "unconnected-(U1A-VCC8-Pad57)") (class "Default")
      (node (ref "U1") (pin "57") (pinfunction "VCC8_57") (pintype "passive+no_connect"))
    )
    (net (code "74") (name "unconnected-(U1B-EXT_EN-Pad60)") (class "Default")
      (node (ref "U1") (pin "60") (pinfunction "EXT_EN_60") (pintype "passive+no_connect"))
    )
  )
)
